# mctrli2c.net
KiCad netlist of a schematic drawn in EAGLE
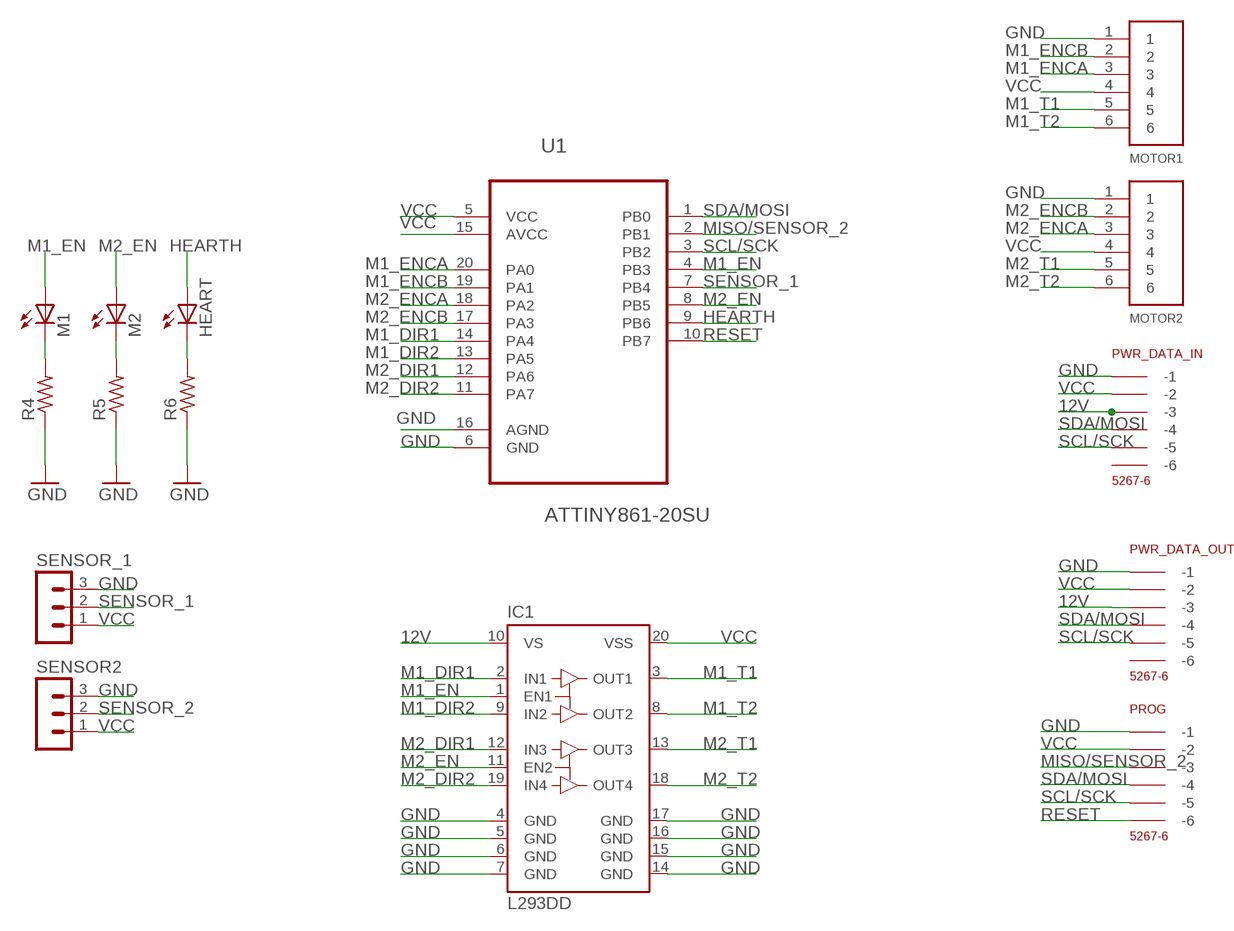
[diagram p0: schematic, sheet 1]

(export (version "E")
  (design (tool "Eeschema 10.0.6"))
  (components
    (comp (ref "HEART")
      (value "LEDSML1206")
      (footprint "eagle-import:SML1206")
      (libsource (lib "eagle-import") (part "LEDSML1206"))
    )
    (comp (ref "IC1")
      (value "L293DD")
      (footprint "eagle-import:SO20")
      (libsource (lib "eagle-import") (part "L293DD"))
    )
    (comp (ref "M1")
      (value "LEDSML1206")
      (footprint "eagle-import:SML1206")
      (libsource (lib "eagle-import") (part "LEDSML1206"))
    )
    (comp (ref "M2")
      (value "LEDSML1206")
      (footprint "eagle-import:SML1206")
      (libsource (lib "eagle-import") (part "LEDSML1206"))
    )
    (comp (ref "MOTOR1")
      (value "6PIN")
      (footprint "eagle-import:B6B-PH-K-S")
      (libsource (lib "eagle-import") (part "6PIN"))
    )
    (comp (ref "MOTOR2")
      (value "6PIN")
      (footprint "eagle-import:B6B-PH-K-S")
      (libsource (lib "eagle-import") (part "6PIN"))
    )
    (comp (ref "PROG")
      (value "5267-6")
      (footprint "eagle-import:5267-6")
      (libsource (lib "eagle-import") (part "5267-6"))
    )
    (comp (ref "PWR_DATA_IN")
      (value "5267-6")
      (footprint "eagle-import:5267-6")
      (libsource (lib "eagle-import") (part "5267-6"))
    )
    (comp (ref "PWR_DATA_OUT")
      (value "5267-6")
      (footprint "eagle-import:5267-6")
      (libsource (lib "eagle-import") (part "5267-6"))
    )
    (comp (ref "R4")
      (value "R-US_R1210")
      (footprint "eagle-import:R1210")
      (libsource (lib "eagle-import") (part "R-US_R1210"))
    )
    (comp (ref "R5")
      (value "R-US_R1210")
      (footprint "eagle-import:R1210")
      (libsource (lib "eagle-import") (part "R-US_R1210"))
    )
    (comp (ref "R6")
      (value "R-US_R1210")
      (footprint "eagle-import:R1210")
      (libsource (lib "eagle-import") (part "R-US_R1210"))
    )
    (comp (ref "SENSOR2")
      (value "MA03-1")
      (footprint "eagle-import:MA03-1")
      (libsource (lib "eagle-import") (part "MA03-1"))
    )
    (comp (ref "SENSOR_1")
      (value "MA03-1")
      (footprint "eagle-import:MA03-1")
      (libsource (lib "eagle-import") (part "MA03-1"))
    )
    (comp (ref "U1")
      (value "ATTINY861-20SU")
      (footprint "eagle-import:SOIC127P1032X265-20N")
      (libsource (lib "eagle-import") (part "ATTINY861-20SU"))
    )
  )
  (nets
    (net (code "1") (name "/12V") (class "Default")
      (node (ref "IC1") (pin "10") (pinfunction "VS_10") (pintype "power_in"))
      (node (ref "PWR_DATA_IN") (pin "P$3") (pinfunction "-3_P$3") (pintype "bidirectional"))
      (node (ref "PWR_DATA_OUT") (pin "P$3") (pinfunction "-3_P$3") (pintype "bidirectional"))
    )
    (net (code "2") (name "/HEARTH") (class "Default")
      (node (ref "HEART") (pin "A") (pinfunction "A_A") (pintype "passive"))
      (node (ref "U1") (pin "9") (pinfunction "PB6_9") (pintype "bidirectional"))
    )
    (net (code "3") (name "/M1_DIR1") (class "Default")
      (node (ref "IC1") (pin "2") (pinfunction "IN1_2") (pintype "input"))
      (node (ref "U1") (pin "14") (pinfunction "PA4_14") (pintype "bidirectional"))
    )
    (net (code "4") (name "/M1_DIR2") (class "Default")
      (node (ref "IC1") (pin "9") (pinfunction "IN2_9") (pintype "input"))
      (node (ref "U1") (pin "13") (pinfunction "PA5_13") (pintype "bidirectional"))
    )
    (net (code "5") (name "/M1_EN") (class "Default")
      (node (ref "IC1") (pin "1") (pinfunction "EN1_1") (pintype "input"))
      (node (ref "M1") (pin "A") (pinfunction "A_A") (pintype "passive"))
      (node (ref "U1") (pin "4") (pinfunction "PB3_4") (pintype "bidirectional"))
    )
    (net (code "6") (name "/M1_ENCA") (class "Default")
      (node (ref "MOTOR1") (pin "3") (pinfunction "3_3") (pintype "bidirectional"))
      (node (ref "U1") (pin "20") (pinfunction "PA0_20") (pintype "bidirectional"))
    )
    (net (code "7") (name "/M1_ENCB") (class "Default")
      (node (ref "MOTOR1") (pin "2") (pinfunction "2_2") (pintype "bidirectional"))
      (node (ref "U1") (pin "19") (pinfunction "PA1_19") (pintype "bidirectional"))
    )
    (net (code "8") (name "/M1_T1") (class "Default")
      (node (ref "IC1") (pin "3") (pinfunction "OUT1_3") (pintype "output"))
      (node (ref "MOTOR1") (pin "5") (pinfunction "5_5") (pintype "bidirectional"))
    )
    (net (code "9") (name "/M1_T2") (class "Default")
      (node (ref "IC1") (pin "8") (pinfunction "OUT2_8") (pintype "output"))
      (node (ref "MOTOR1") (pin "6") (pinfunction "6_6") (pintype "bidirectional"))
    )
    (net (code "10") (name "/M2_DIR1") (class "Default")
      (node (ref "IC1") (pin "12") (pinfunction "IN3_12") (pintype "input"))
      (node (ref "U1") (pin "12") (pinfunction "PA6_12") (pintype "bidirectional"))
    )
    (net (code "11") (name "/M2_DIR2") (class "Default")
      (node (ref "IC1") (pin "19") (pinfunction "IN4_19") (pintype "input"))
      (node (ref "U1") (pin "11") (pinfunction "PA7_11") (pintype "bidirectional"))
    )
    (net (code "12") (name "/M2_EN") (class "Default")
      (node (ref "IC1") (pin "11") (pinfunction "EN2_11") (pintype "input"))
      (node (ref "M2") (pin "A") (pinfunction "A_A") (pintype "passive"))
      (node (ref "U1") (pin "8") (pinfunction "PB5_8") (pintype "bidirectional"))
    )
    (net (code "13") (name "/M2_ENCA") (class "Default")
      (node (ref "MOTOR2") (pin "3") (pinfunction "3_3") (pintype "bidirectional"))
      (node (ref "U1") (pin "18") (pinfunction "PA2_18") (pintype "bidirectional"))
    )
    (net (code "14") (name "/M2_ENCB") (class "Default")
      (node (ref "MOTOR2") (pin "2") (pinfunction "2_2") (pintype "bidirectional"))
      (node (ref "U1") (pin "17") (pinfunction "PA3_17") (pintype "bidirectional"))
    )
    (net (code "15") (name "/M2_T1") (class "Default")
      (node (ref "IC1") (pin "13") (pinfunction "OUT3_13") (pintype "output"))
      (node (ref "MOTOR2") (pin "5") (pinfunction "5_5") (pintype "bidirectional"))
    )
    (net (code "16") (name "/M2_T2") (class "Default")
      (node (ref "IC1") (pin "18") (pinfunction "OUT4_18") (pintype "output"))
      (node (ref "MOTOR2") (pin "6") (pinfunction "6_6") (pintype "bidirectional"))
    )
    (net (code "17") (name "/MISO{slash}SENSOR_2") (class "Default")
      (node (ref "PROG") (pin "P$3") (pinfunction "-3_P$3") (pintype "bidirectional"))
      (node (ref "U1") (pin "2") (pinfunction "PB1_2") (pintype "bidirectional"))
    )
    (net (code "18") (name "/RESET") (class "Default")
      (node (ref "PROG") (pin "P$6") (pinfunction "-6_P$6") (pintype "bidirectional"))
      (node (ref "U1") (pin "10") (pinfunction "PB7_10") (pintype "bidirectional"))
    )
    (net (code "19") (name "/SCL{slash}SCK") (class "Default")
      (node (ref "PROG") (pin "P$5") (pinfunction "-5_P$5") (pintype "bidirectional"))
      (node (ref "PWR_DATA_IN") (pin "P$5") (pinfunction "-5_P$5") (pintype "bidirectional"))
      (node (ref "PWR_DATA_OUT") (pin "P$5") (pinfunction "-5_P$5") (pintype "bidirectional"))
      (node (ref "U1") (pin "3") (pinfunction "PB2_3") (pintype "bidirectional"))
    )
    (net (code "20") (name "/SDA{slash}MOSI") (class "Default")
      (node (ref "PROG") (pin "P$4") (pinfunction "-4_P$4") (pintype "bidirectional"))
      (node (ref "PWR_DATA_IN") (pin "P$4") (pinfunction "-4_P$4") (pintype "bidirectional"))
      (node (ref "PWR_DATA_OUT") (pin "P$4") (pinfunction "-4_P$4") (pintype "bidirectional"))
      (node (ref "U1") (pin "1") (pinfunction "PB0_1") (pintype "bidirectional"))
    )
    (net (code "21") (name "/SENSOR_1") (class "Default")
      (node (ref "SENSOR_1") (pin "2") (pinfunction "2_2") (pintype "passive"))
      (node (ref "U1") (pin "7") (pinfunction "PB4_7") (pintype "bidirectional"))
    )
    (net (code "22") (name "/SENSOR_2") (class "Default")
      (node (ref "SENSOR2") (pin "2") (pinfunction "2_2") (pintype "passive"))
    )
    (net (code "23") (name "/VCC") (class "Default")
      (node (ref "IC1") (pin "20") (pinfunction "VSS_20") (pintype "power_in"))
      (node (ref "MOTOR1") (pin "4") (pinfunction "4_4") (pintype "bidirectional"))
      (node (ref "MOTOR2") (pin "4") (pinfunction "4_4") (pintype "bidirectional"))
      (node (ref "PROG") (pin "P$2") (pinfunction "-2_P$2") (pintype "bidirectional"))
      (node (ref "PWR_DATA_IN") (pin "P$2") (pinfunction "-2_P$2") (pintype "bidirectional"))
      (node (ref "PWR_DATA_OUT") (pin "P$2") (pinfunction "-2_P$2") (pintype "bidirectional"))
      (node (ref "SENSOR2") (pin "1") (pinfunction "1_1") (pintype "passive"))
      (node (ref "SENSOR_1") (pin "1") (pinfunction "1_1") (pintype "passive"))
      (node (ref "U1") (pin "15") (pinfunction "AVCC_15") (pintype "power_in"))
      (node (ref "U1") (pin "5") (pinfunction "VCC_5") (pintype "power_in"))
    )
    (net (code "24") (name "GND") (class "Default")
      (node (ref "IC1") (pin "14") (pinfunction "GND_14") (pintype "power_in"))
      (node (ref "IC1") (pin "15") (pinfunction "GND_15") (pintype "power_in"))
      (node (ref "IC1") (pin "16") (pinfunction "GND_16") (pintype "power_in"))
      (node (ref "IC1") (pin "17") (pinfunction "GND_17") (pintype "power_in"))
      (node (ref "IC1") (pin "4") (pinfunction "GND_4") (pintype "power_in"))
      (node (ref "IC1") (pin "5") (pinfunction "GND_5") (pintype "power_in"))
      (node (ref "IC1") (pin "6") (pinfunction "GND_6") (pintype "power_in"))
      (node (ref "IC1") (pin "7") (pinfunction "GND_7") (pintype "power_in"))
      (node (ref "MOTOR1") (pin "1") (pinfunction "1_1") (pintype "bidirectional"))
      (node (ref "MOTOR2") (pin "1") (pinfunction "1_1") (pintype "bidirectional"))
      (node (ref "PROG") (pin "P$1") (pinfunction "-1_P$1") (pintype "bidirectional"))
      (node (ref "PWR_DATA_IN") (pin "P$1") (pinfunction "-1_P$1") (pintype "bidirectional"))
      (node (ref "PWR_DATA_OUT") (pin "P$1") (pinfunction "-1_P$1") (pintype "bidirectional"))
      (node (ref "R4") (pin "1") (pinfunction "1_1") (pintype "passive"))
      (node (ref "R5") (pin "1") (pinfunction "1_1") (pintype "passive"))
      (node (ref "R6") (pin "1") (pinfunction "1_1") (pintype "passive"))
      (node (ref "SENSOR2") (pin "3") (pinfunction "3_3") (pintype "passive"))
      (node (ref "SENSOR_1") (pin "3") (pinfunction "3_3") (pintype "passive"))
      (node (ref "U1") (pin "16") (pinfunction "AGND_16") (pintype "passive"))
      (node (ref "U1") (pin "6") (pinfunction "GND_6") (pintype "passive"))
    )
    (net (code "25") (name "Net-(HEART-PadC)") (class "Default")
      (node (ref "HEART") (pin "C") (pinfunction "C_C") (pintype "passive"))
      (node (ref "R6") (pin "2") (pinfunction "2_2") (pintype "passive"))
    )
    (net (code "26") (name "Net-(M1-PadC)") (class "Default")
      (node (ref "M1") (pin "C") (pinfunction "C_C") (pintype "passive"))
      (node (ref "R4") (pin "2") (pinfunction "2_2") (pintype "passive"))
    )
    (net (code "27") (name "Net-(M2-PadC)") (class "Default")
      (node (ref "M2") (pin "C") (pinfunction "C_C") (pintype "passive"))
      (node (ref "R5") (pin "2") (pinfunction "2_2") (pintype "passive"))
    )
    (net (code "28") (name "unconnected-(PWR_DATA_IN--6-PadP$6)") (class "Default")
      (node (ref "PWR_DATA_IN") (pin "P$6") (pinfunction "-6_P$6") (pintype "bidirectional"))
    )
    (net (code "29") (name "unconnected-(PWR_DATA_OUT--6-PadP$6)") (class "Default")
      (node (ref "PWR_DATA_OUT") (pin "P$6") (pinfunction "-6_P$6") (pintype "bidirectional"))
    )
  )
)
